# LogiTemp.net
KiCad netlist of a schematic drawn in Altium Designer
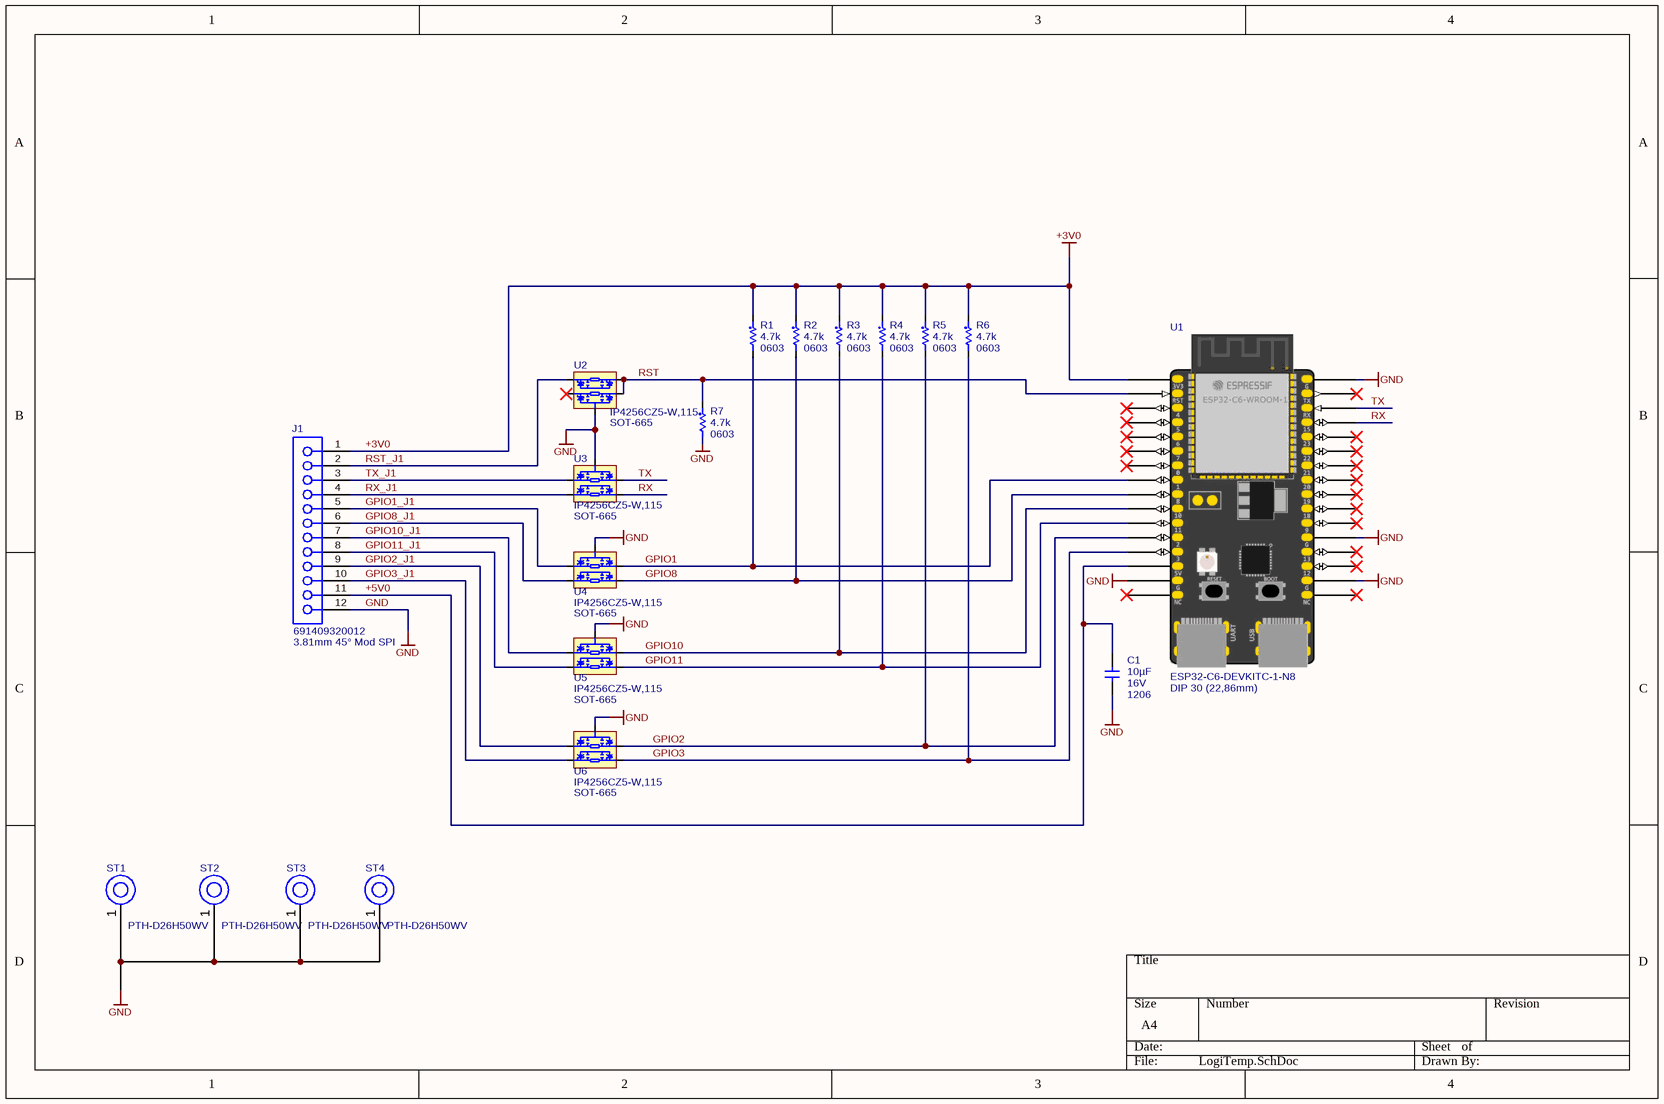
[diagram p0: LogiTemp.SchDoc]

(export (version "E")
  (design (tool "Eeschema 10.0.6"))
  (components
    (comp (ref "C1")
      (value "10µF")
      (footprint "C1206_IPC_B_3.2x1.6x1.60mm")
      (description "CAP CER 10µF 16V ±10% X7R 1206")
      (fields
        (field (name "VOLTAGE RATING") "16V")
        (field (name "CASE/PACKAGE") "1206")
        (field (name "TOLERANCE") "10%")
      )
      (libsource (lib "Altium Concord Pro on A365") (part "STD SYMBOL CAP NON POL"))
    )
    (comp (ref "J1")
      (value "691409320012")
      (footprint "691409320012")
      (description "Terminal Block, Wtb, 12POS, 26-16AWG;")
      (fields (field (name "CASE/PACKAGE") "3.81mm 45° Mod SPI"))
      (libsource (lib "Altium Concord Pro on A365") (part "691401700012B"))
    )
    (comp (ref "R1")
      (value "4.7k")
      (footprint "R0603_IPC_B_1.55x0.8x0.55mm")
      (description "RES SMD 4.7k 1% 1/4W 0603")
      (fields
        (field (name "CASE/PACKAGE") "0603")
        (field (name "TOLERANCE") "1%")
        (field (name "POWER") "250mW")
      )
      (libsource (lib "Altium Concord Pro on A365") (part "RES-2"))
    )
    (comp (ref "R2")
      (value "4.7k")
      (footprint "R0603_IPC_B_1.55x0.8x0.55mm")
      (description "RES SMD 4.7k 1% 1/4W 0603")
      (fields
        (field (name "CASE/PACKAGE") "0603")
        (field (name "TOLERANCE") "1%")
        (field (name "POWER") "250mW")
      )
      (libsource (lib "Altium Concord Pro on A365") (part "RES-2"))
    )
    (comp (ref "R3")
      (value "4.7k")
      (footprint "R0603_IPC_B_1.55x0.8x0.55mm")
      (description "RES SMD 4.7k 1% 1/4W 0603")
      (fields
        (field (name "CASE/PACKAGE") "0603")
        (field (name "TOLERANCE") "1%")
        (field (name "POWER") "250mW")
      )
      (libsource (lib "Altium Concord Pro on A365") (part "RES-2"))
    )
    (comp (ref "R4")
      (value "4.7k")
      (footprint "R0603_IPC_B_1.55x0.8x0.55mm")
      (description "RES SMD 4.7k 1% 1/4W 0603")
      (fields
        (field (name "CASE/PACKAGE") "0603")
        (field (name "TOLERANCE") "1%")
        (field (name "POWER") "250mW")
      )
      (libsource (lib "Altium Concord Pro on A365") (part "RES-2"))
    )
    (comp (ref "R5")
      (value "4.7k")
      (footprint "R0603_IPC_B_1.55x0.8x0.55mm")
      (description "RES SMD 4.7k 1% 1/4W 0603")
      (fields
        (field (name "CASE/PACKAGE") "0603")
        (field (name "TOLERANCE") "1%")
        (field (name "POWER") "250mW")
      )
      (libsource (lib "Altium Concord Pro on A365") (part "RES-2"))
    )
    (comp (ref "R6")
      (value "4.7k")
      (footprint "R0603_IPC_B_1.55x0.8x0.55mm")
      (description "RES SMD 4.7k 1% 1/4W 0603")
      (fields
        (field (name "CASE/PACKAGE") "0603")
        (field (name "TOLERANCE") "1%")
        (field (name "POWER") "250mW")
      )
      (libsource (lib "Altium Concord Pro on A365") (part "RES-2"))
    )
    (comp (ref "R7")
      (value "4.7k")
      (footprint "R0603_IPC_B_1.55x0.8x0.55mm")
      (description "RES SMD 4.7k 1% 1/4W 0603")
      (fields
        (field (name "CASE/PACKAGE") "0603")
        (field (name "TOLERANCE") "1%")
        (field (name "POWER") "250mW")
      )
      (libsource (lib "Altium Concord Pro on A365") (part "RES-2"))
    )
    (comp (ref "ST1")
      (value "PTH-D26H50WV")
      (footprint "PTH-D26H50WV")
      (libsource (lib "Altium Concord Pro on A365") (part "CMP-00028-00000-1"))
    )
    (comp (ref "ST2")
      (value "PTH-D26H50WV")
      (footprint "PTH-D26H50WV")
      (libsource (lib "Altium Concord Pro on A365") (part "CMP-00028-00000-1"))
    )
    (comp (ref "ST3")
      (value "PTH-D26H50WV")
      (footprint "PTH-D26H50WV")
      (libsource (lib "Altium Concord Pro on A365") (part "CMP-00028-00000-1"))
    )
    (comp (ref "ST4")
      (value "PTH-D26H50WV")
      (footprint "PTH-D26H50WV")
      (libsource (lib "Altium Concord Pro on A365") (part "CMP-00028-00000-1"))
    )
    (comp (ref "U1")
      (value "ESP32-C6-DEVKITC-1-N8")
      (footprint "ESP32-C6-DEVKITC-1-N8")
      (description "ESP32-C6 General-purpose Develop")
      (fields (field (name "CASE/PACKAGE") "DIP 30 (22,86mm)") (field (name "POWER") "2.64W"))
      (libsource (lib "Altium Concord Pro on A365") (part "ESP32-C6-DevKitC-1"))
    )
    (comp (ref "U2")
      (value "IP4256CZ5-W,115")
      (footprint "SOT665_NXP")
      (description "NXP IP4256CZ5-W, Dual Uni-Directional EMI Filter & ESD Protector, 120mW, 5-Pin SOT-665")
      (fields (field (name "CASE/PACKAGE") "SOT-665"))
      (libsource (lib "Altium Concord Pro on A365") (part "IP4256CZ5-W,115"))
    )
    (comp (ref "U3")
      (value "IP4256CZ5-W,115")
      (footprint "SOT665_NXP")
      (description "NXP IP4256CZ5-W, Dual Uni-Directional EMI Filter & ESD Protector, 120mW, 5-Pin SOT-665")
      (fields (field (name "CASE/PACKAGE") "SOT-665"))
      (libsource (lib "Altium Concord Pro on A365") (part "IP4256CZ5-W,115"))
    )
    (comp (ref "U4")
      (value "IP4256CZ5-W,115")
      (footprint "SOT665_NXP")
      (description "NXP IP4256CZ5-W, Dual Uni-Directional EMI Filter & ESD Protector, 120mW, 5-Pin SOT-665")
      (fields (field (name "CASE/PACKAGE") "SOT-665"))
      (libsource (lib "Altium Concord Pro on A365") (part "IP4256CZ5-W,115"))
    )
    (comp (ref "U5")
      (value "IP4256CZ5-W,115")
      (footprint "SOT665_NXP")
      (description "NXP IP4256CZ5-W, Dual Uni-Directional EMI Filter & ESD Protector, 120mW, 5-Pin SOT-665")
      (fields (field (name "CASE/PACKAGE") "SOT-665"))
      (libsource (lib "Altium Concord Pro on A365") (part "IP4256CZ5-W,115"))
    )
    (comp (ref "U6")
      (value "IP4256CZ5-W,115")
      (footprint "SOT665_NXP")
      (description "NXP IP4256CZ5-W, Dual Uni-Directional EMI Filter & ESD Protector, 120mW, 5-Pin SOT-665")
      (fields (field (name "CASE/PACKAGE") "SOT-665"))
      (libsource (lib "Altium Concord Pro on A365") (part "IP4256CZ5-W,115"))
    )
  )
  (nets
    (net (code "1") (name "+3V0") (class "Default")
      (node (ref "J1") (pin "1") (pinfunction "1_1") (pintype "passive"))
      (node (ref "R1") (pin "1") (pinfunction "1_1") (pintype "passive"))
      (node (ref "R2") (pin "1") (pinfunction "1_1") (pintype "passive"))
      (node (ref "R3") (pin "1") (pinfunction "1_1") (pintype "passive"))
      (node (ref "R4") (pin "1") (pinfunction "1_1") (pintype "passive"))
      (node (ref "R5") (pin "1") (pinfunction "1_1") (pintype "passive"))
      (node (ref "R6") (pin "1") (pinfunction "1_1") (pintype "passive"))
      (node (ref "U1") (pin "1") (pinfunction "3V3_1") (pintype "power_in"))
    )
    (net (code "2") (name "/+5V0") (class "Default")
      (node (ref "C1") (pin "1") (pinfunction "1_1") (pintype "passive"))
      (node (ref "J1") (pin "11") (pinfunction "11_11") (pintype "passive"))
      (node (ref "U1") (pin "14") (pinfunction "5V0_14") (pintype "power_in"))
    )
    (net (code "3") (name "/GPIO1") (class "Default")
      (node (ref "R1") (pin "2") (pinfunction "2_2") (pintype "passive"))
      (node (ref "U1") (pin "8") (pinfunction "1/N_8") (pintype "bidirectional"))
      (node (ref "U4") (pin "5") (pinfunction "5_5") (pintype "passive"))
    )
    (net (code "4") (name "/GPIO1_J1") (class "Default")
      (node (ref "J1") (pin "5") (pinfunction "5_5") (pintype "passive"))
      (node (ref "U4") (pin "1") (pinfunction "1_1") (pintype "passive"))
    )
    (net (code "5") (name "/GPIO2") (class "Default")
      (node (ref "R5") (pin "2") (pinfunction "2_2") (pintype "passive"))
      (node (ref "U1") (pin "12") (pinfunction "14_12") (pintype "bidirectional"))
      (node (ref "U6") (pin "5") (pinfunction "5_5") (pintype "passive"))
    )
    (net (code "6") (name "/GPIO2_J1") (class "Default")
      (node (ref "J1") (pin "9") (pinfunction "9_9") (pintype "passive"))
      (node (ref "U6") (pin "1") (pinfunction "1_1") (pintype "passive"))
    )
    (net (code "7") (name "/GPIO3") (class "Default")
      (node (ref "R6") (pin "2") (pinfunction "2_2") (pintype "passive"))
      (node (ref "U1") (pin "13") (pinfunction "GND_13") (pintype "bidirectional"))
      (node (ref "U6") (pin "4") (pinfunction "4_4") (pintype "passive"))
    )
    (net (code "8") (name "/GPIO3_J1") (class "Default")
      (node (ref "J1") (pin "10") (pinfunction "10_10") (pintype "passive"))
      (node (ref "U6") (pin "3") (pinfunction "3_3") (pintype "passive"))
    )
    (net (code "9") (name "/GPIO8") (class "Default")
      (node (ref "R2") (pin "2") (pinfunction "2_2") (pintype "passive"))
      (node (ref "U1") (pin "9") (pinfunction "8_9") (pintype "bidirectional"))
      (node (ref "U4") (pin "4") (pinfunction "4_4") (pintype "passive"))
    )
    (net (code "10") (name "/GPIO8_J1") (class "Default")
      (node (ref "J1") (pin "6") (pinfunction "6_6") (pintype "passive"))
      (node (ref "U4") (pin "3") (pinfunction "3_3") (pintype "passive"))
    )
    (net (code "11") (name "/GPIO10") (class "Default")
      (node (ref "R3") (pin "2") (pinfunction "2_2") (pintype "passive"))
      (node (ref "U1") (pin "10") (pinfunction "6_10") (pintype "bidirectional"))
      (node (ref "U5") (pin "5") (pinfunction "5_5") (pintype "passive"))
    )
    (net (code "12") (name "/GPIO10_J1") (class "Default")
      (node (ref "J1") (pin "7") (pinfunction "7_7") (pintype "passive"))
      (node (ref "U5") (pin "1") (pinfunction "1_1") (pintype "passive"))
    )
    (net (code "13") (name "/GPIO11") (class "Default")
      (node (ref "R4") (pin "2") (pinfunction "2_2") (pintype "passive"))
      (node (ref "U1") (pin "11") (pinfunction "7_11") (pintype "bidirectional"))
      (node (ref "U5") (pin "4") (pinfunction "4_4") (pintype "passive"))
    )
    (net (code "14") (name "/GPIO11_J1") (class "Default")
      (node (ref "J1") (pin "8") (pinfunction "8_8") (pintype "passive"))
      (node (ref "U5") (pin "3") (pinfunction "3_3") (pintype "passive"))
    )
    (net (code "15") (name "/RST") (class "Default")
      (node (ref "R7") (pin "1") (pinfunction "1_1") (pintype "passive"))
      (node (ref "U1") (pin "2") (pinfunction "RST_2") (pintype "input"))
      (node (ref "U2") (pin "4") (pinfunction "4_4") (pintype "passive"))
      (node (ref "U2") (pin "5") (pinfunction "5_5") (pintype "passive"))
    )
    (net (code "16") (name "/RST_J1") (class "Default")
      (node (ref "J1") (pin "2") (pinfunction "2_2") (pintype "passive"))
      (node (ref "U2") (pin "3") (pinfunction "3_3") (pintype "passive"))
    )
    (net (code "17") (name "/RX") (class "Default")
      (node (ref "U1") (pin "29") (pinfunction "15_29") (pintype "bidirectional"))
      (node (ref "U3") (pin "4") (pinfunction "4_4") (pintype "passive"))
    )
    (net (code "18") (name "/RX_J1") (class "Default")
      (node (ref "J1") (pin "4") (pinfunction "4_4") (pintype "passive"))
      (node (ref "U3") (pin "3") (pinfunction "3_3") (pintype "passive"))
    )
    (net (code "19") (name "/TX") (class "Default")
      (node (ref "U1") (pin "30") (pinfunction "RX_30") (pintype "input"))
      (node (ref "U3") (pin "5") (pinfunction "5_5") (pintype "passive"))
    )
    (net (code "20") (name "/TX_J1") (class "Default")
      (node (ref "J1") (pin "3") (pinfunction "3_3") (pintype "passive"))
      (node (ref "U3") (pin "1") (pinfunction "1_1") (pintype "passive"))
    )
    (net (code "21") (name "GND") (class "Default")
      (node (ref "C1") (pin "2") (pinfunction "2_2") (pintype "passive"))
      (node (ref "J1") (pin "12") (pinfunction "12_12") (pintype "passive"))
      (node (ref "R7") (pin "2") (pinfunction "2_2") (pintype "passive"))
      (node (ref "ST1") (pin "1") (pinfunction "H1_1") (pintype "passive"))
      (node (ref "ST2") (pin "1") (pinfunction "H1_1") (pintype "passive"))
      (node (ref "ST3") (pin "1") (pinfunction "H1_1") (pintype "passive"))
      (node (ref "ST4") (pin "1") (pinfunction "H1_1") (pintype "passive"))
      (node (ref "U1") (pin "15") (pinfunction "GND_15") (pintype "power_in"))
      (node (ref "U1") (pin "18") (pinfunction "GND_18") (pintype "power_in"))
      (node (ref "U1") (pin "21") (pinfunction "GND_21") (pintype "power_in"))
      (node (ref "U1") (pin "32") (pinfunction "GND_32") (pintype "power_in"))
      (node (ref "U2") (pin "2") (pinfunction "PAD_2") (pintype "passive"))
      (node (ref "U3") (pin "2") (pinfunction "PAD_2") (pintype "passive"))
      (node (ref "U4") (pin "2") (pinfunction "PAD_2") (pintype "passive"))
      (node (ref "U5") (pin "2") (pinfunction "PAD_2") (pintype "passive"))
      (node (ref "U6") (pin "2") (pinfunction "PAD_2") (pintype "passive"))
    )
    (net (code "22") (name "unconnected-(U1-0{slash}N-Pad7)") (class "Default")
      (node (ref "U1") (pin "7") (pinfunction "0/N_7") (pintype "bidirectional+no_connect"))
    )
    (net (code "23") (name "unconnected-(U1-2-Pad3)") (class "Default")
      (node (ref "U1") (pin "3") (pinfunction "2_3") (pintype "bidirectional+no_connect"))
    )
    (net (code "24") (name "unconnected-(U1-3-Pad4)") (class "Default")
      (node (ref "U1") (pin "4") (pinfunction "3_4") (pintype "bidirectional+no_connect"))
    )
    (net (code "25") (name "unconnected-(U1-4-Pad5)") (class "Default")
      (node (ref "U1") (pin "5") (pinfunction "4_5") (pintype "bidirectional+no_connect"))
    )
    (net (code "26") (name "unconnected-(U1-5-Pad6)") (class "Default")
      (node (ref "U1") (pin "6") (pinfunction "5_6") (pintype "bidirectional+no_connect"))
    )
    (net (code "27") (name "unconnected-(U1-9-Pad22)") (class "Default")
      (node (ref "U1") (pin "22") (pinfunction "9_22") (pintype "bidirectional+no_connect"))
    )
    (net (code "28") (name "unconnected-(U1-12-Pad19)") (class "Default")
      (node (ref "U1") (pin "19") (pinfunction "12_19") (pintype "bidirectional+no_connect"))
    )
    (net (code "29") (name "unconnected-(U1-13-Pad20)") (class "Default")
      (node (ref "U1") (pin "20") (pinfunction "13_20") (pintype "bidirectional+no_connect"))
    )
    (net (code "30") (name "unconnected-(U1-18-Pad23)") (class "Default")
      (node (ref "U1") (pin "23") (pinfunction "18_23") (pintype "bidirectional+no_connect"))
    )
    (net (code "31") (name "unconnected-(U1-19-Pad24)") (class "Default")
      (node (ref "U1") (pin "24") (pinfunction "19_24") (pintype "bidirectional+no_connect"))
    )
    (net (code "32") (name "unconnected-(U1-20-Pad25)") (class "Default")
      (node (ref "U1") (pin "25") (pinfunction "20_25") (pintype "bidirectional+no_connect"))
    )
    (net (code "33") (name "unconnected-(U1-21-Pad26)") (class "Default")
      (node (ref "U1") (pin "26") (pinfunction "21_26") (pintype "bidirectional+no_connect"))
    )
    (net (code "34") (name "unconnected-(U1-22-Pad27)") (class "Default")
      (node (ref "U1") (pin "27") (pinfunction "22_27") (pintype "bidirectional+no_connect"))
    )
    (net (code "35") (name "unconnected-(U1-23-Pad28)") (class "Default")
      (node (ref "U1") (pin "28") (pinfunction "23_28") (pintype "bidirectional+no_connect"))
    )
    (net (code "36") (name "unconnected-(U1-NC-Pad16)") (class "Default")
      (node (ref "U1") (pin "16") (pinfunction "NC_16") (pintype "passive+no_connect"))
    )
    (net (code "37") (name "unconnected-(U1-NC-Pad17)") (class "Default")
      (node (ref "U1") (pin "17") (pinfunction "NC_17") (pintype "passive+no_connect"))
    )
    (net (code "38") (name "unconnected-(U1-TX-Pad31)") (class "Default")
      (node (ref "U1") (pin "31") (pinfunction "TX_31") (pintype "output+no_connect"))
    )
    (net (code "39") (name "unconnected-(U2-Pad1)") (class "Default")
      (node (ref "U2") (pin "1") (pinfunction "1_1") (pintype "passive+no_connect"))
    )
  )
)
